# DM2080_Power_Supply.net
KiCad netlist of a schematic drawn in Altium Designer
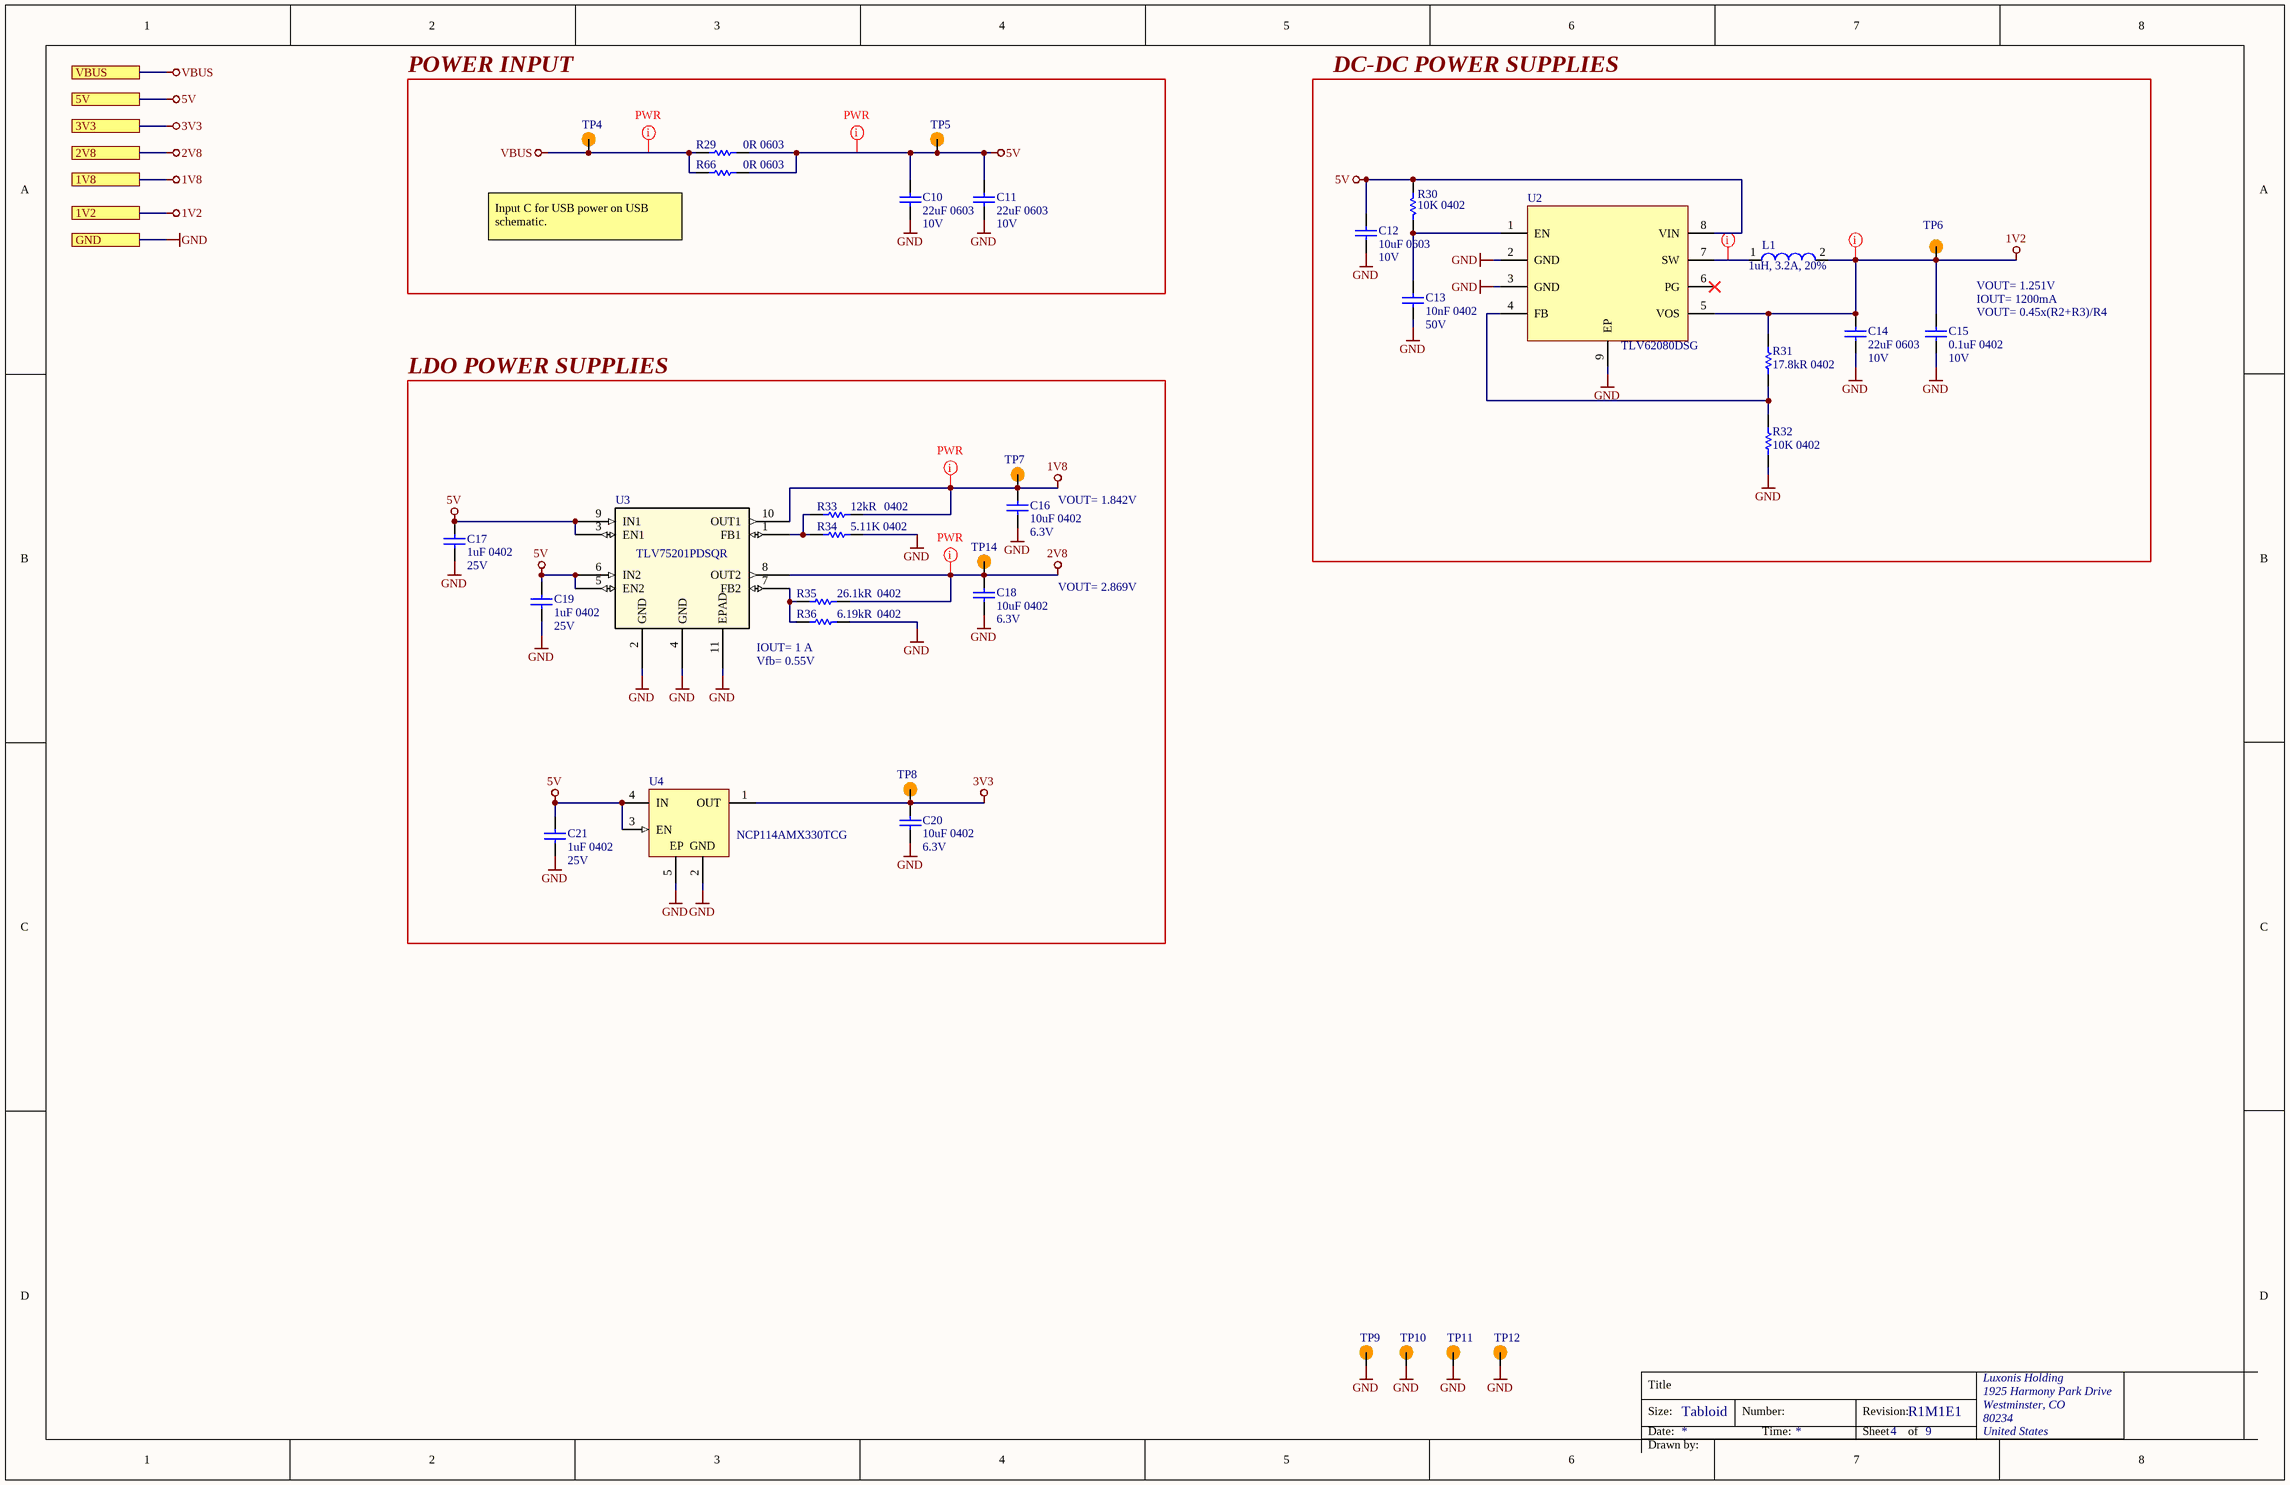
[diagram p0: DM2080_Power_Supply.SchDoc]

(export (version "E")
  (design (tool "Eeschema 10.0.6"))
  (components
    (comp (ref "C10")
      (value "22uF 0603")
      (footprint "CAP_Altium_Vault_Generic:CAPC0603(1608)100_L")
      (description "CAP CER 22UF 10V X5R 0603 20%")
      (fields (field (name "TOLERANCE") "20%") (field (name "VOLTAGE RATING") "10V"))
      (libsource (lib "LuxonisMaster") (part "GRM188R61A226ME15D"))
    )
    (comp (ref "C11")
      (value "22uF 0603")
      (footprint "CAP_Altium_Vault_Generic:CAPC0603(1608)100_L")
      (description "CAP CER 22UF 10V X5R 0603 20%")
      (fields (field (name "TOLERANCE") "20%") (field (name "VOLTAGE RATING") "10V"))
      (libsource (lib "LuxonisMaster") (part "GRM188R61A226ME15D"))
    )
    (comp (ref "C12")
      (value "10uF 0603")
      (footprint "CAP_Altium_Vault_Generic:CAPC0603(1608)100_L")
      (description "CAP CER 10UF 10V X5R 0603 20%")
      (fields (field (name "TOLERANCE") "20%") (field (name "VOLTAGE RATING") "10V"))
      (libsource (lib "LuxonisMaster") (part "GRM188R61A106ME69D"))
    )
    (comp (ref "C13")
      (value "10nF 0402")
      (footprint "CAP_Altium_Vault_Generic:CAPC0402(1005)60_L")
      (description "CAP CER 10000PF 50V X7R 0402")
      (fields
        (field (name "TOLERANCE") "10%")
        (field (name "VOLTAGE") "25V")
        (field (name "VOLTAGE RATING") "50V")
      )
      (libsource (lib "LuxonisMaster") (part "GRM155R71H103KA88D"))
    )
    (comp (ref "C14")
      (value "22uF 0603")
      (footprint "CAP_Altium_Vault_Generic:CAPC0603(1608)100_L")
      (description "CAP CER 22UF 10V X5R 0603 20%")
      (fields (field (name "TOLERANCE") "20%") (field (name "VOLTAGE RATING") "10V"))
      (libsource (lib "LuxonisMaster") (part "GRM188R61A226ME15D"))
    )
    (comp (ref "C15")
      (value "0.1uF 0402")
      (footprint "CAP_Altium_Vault_Generic:CAPC0402(1005)70_L")
      (description "CAP CER 0.1UF 10V X7R 0402 5%")
      (fields (field (name "TOLERANCE") "5%") (field (name "VOLTAGE RATING") "10V"))
      (libsource (lib "LuxonisMaster") (part "GRM155R71A104JA01D"))
    )
    (comp (ref "C16")
      (value "10uF 0402")
      (footprint "CAP_Altium_Vault_Generic:CAPC0402(1005)70_L")
      (description "CAP CER 10UF 6.3V X5R 0402 20%")
      (fields (field (name "TOLERANCE") "20%") (field (name "VOLTAGE RATING") "6.3V"))
      (libsource (lib "LuxonisMaster") (part "GRM155R60J106ME15D"))
    )
    (comp (ref "C17")
      (value "1uF 0402")
      (footprint "CAP_Altium_Vault_Generic:CAPC0402(1005)70_L")
      (description "CAP CER 1UF 25V X5R 0402 10%")
      (fields
        (field (name "TOLERANCE") "10%")
        (field (name "VOLTAGE RATING") "25V")
        (field (name "VOLTAGE") "25V")
      )
      (libsource (lib "LuxonisMaster") (part "GRM155R61E105KA12D"))
    )
    (comp (ref "C18")
      (value "10uF 0402")
      (footprint "CAP_Altium_Vault_Generic:CAPC0402(1005)70_L")
      (description "CAP CER 10UF 6.3V X5R 0402 20%")
      (fields (field (name "TOLERANCE") "20%") (field (name "VOLTAGE RATING") "6.3V"))
      (libsource (lib "LuxonisMaster") (part "GRM155R60J106ME15D"))
    )
    (comp (ref "C19")
      (value "1uF 0402")
      (footprint "CAP_Altium_Vault_Generic:CAPC0402(1005)70_L")
      (description "CAP CER 1UF 25V X5R 0402 10%")
      (fields
        (field (name "TOLERANCE") "10%")
        (field (name "VOLTAGE RATING") "25V")
        (field (name "VOLTAGE") "25V")
      )
      (libsource (lib "LuxonisMaster") (part "GRM155R61E105KA12D"))
    )
    (comp (ref "C20")
      (value "10uF 0402")
      (footprint "CAP_Altium_Vault_Generic:CAPC0402(1005)70_L")
      (description "CAP CER 10UF 6.3V X5R 0402 20%")
      (fields (field (name "TOLERANCE") "20%") (field (name "VOLTAGE RATING") "6.3V"))
      (libsource (lib "LuxonisMaster") (part "GRM155R60J106ME15D"))
    )
    (comp (ref "C21")
      (value "1uF 0402")
      (footprint "CAP_Altium_Vault_Generic:CAPC0402(1005)70_L")
      (description "CAP CER 1UF 25V X5R 0402 10%")
      (fields
        (field (name "TOLERANCE") "10%")
        (field (name "VOLTAGE RATING") "25V")
        (field (name "VOLTAGE") "25V")
      )
      (libsource (lib "LuxonisMaster") (part "GRM155R61E105KA12D"))
    )
    (comp (ref "L1")
      (value "1uH, 3.2A, 20%")
      (footprint "LuxonisMaster:DFE252012P-1R0M=P2")
      (description "FIXED IND 1UH 3.2A 42 MOHM SMD")
      (fields (field (name "TOLERANCE") "20%") (field (name "MANUFACTURER") "Murata"))
      (libsource (lib "LuxonisMaster") (part "DFE252012P-1R0M=P2"))
    )
    (comp (ref "R29")
      (value "0R 0603")
      (footprint "RES_Altium_Vault_Generic:RESC0603(1608)_N")
      (fields (field (name "TOLERANCE") "5%"))
      (libsource (lib "LuxonisMaster") (part "CRCW06030000Z0EA"))
    )
    (comp (ref "R30")
      (value "10K 0402")
      (footprint "RES_Altium_Vault_Generic:RESC0402(1005)_L")
      (fields (field (name "TOLERANCE") "1%"))
      (libsource (lib "LuxonisMaster") (part "RC0402FR-1310KL"))
    )
    (comp (ref "R31")
      (value "ERJ-2RKF1782X")
      (footprint "RESC0402(1005)_L")
      (fields
        (field (name "CASE/PACKAGE") "0402")
        (field (name "TOLERANCE") "1%")
        (field (name "RESISTANCE") "17.8kR")
      )
      (libsource (lib "Luxonis LLC") (part "CR0402-FX-2492GLF"))
    )
    (comp (ref "R32")
      (value "10K 0402")
      (footprint "RES_Altium_Vault_Generic:RESC0402(1005)_L")
      (description "RES SMD 10K OHM 1% 1/16W 0402")
      (fields (field (name "TOLERANCE") "1%"))
      (libsource (lib "LuxonisMaster") (part "RC0402FR-1310KL"))
    )
    (comp (ref "R33")
      (value "RC0402FR-0712KL")
      (footprint "RESC0402(1005)_L")
      (fields
        (field (name "TOLERANCE") "1%")
        (field (name "RESISTANCE") "12kR")
        (field (name "CASE/PACKAGE") "0402")
      )
      (libsource (lib "Luxonis LLC") (part "CR0402-FX-2492GLF"))
    )
    (comp (ref "R34")
      (value "5.11K 0402")
      (footprint "RES_Altium_Vault_Generic:RESC0402(1005)_L")
      (fields (field (name "TOLERANCE") "1%"))
      (libsource (lib "LuxonisMaster") (part "RC0402FR-075K11L"))
    )
    (comp (ref "R35")
      (value "RC0402FR-0726K1L")
      (footprint "RESC0402(1005)_L")
      (description "RES SMD 26.1K OHM 1% 1/16W 0402")
      (fields
        (field (name "CASE/PACKAGE") "0402")
        (field (name "TOLERANCE") "1%")
        (field (name "RESISTANCE") "26.1kR")
      )
      (libsource (lib "Luxonis LLC") (part "RC0402FR-0726K1L"))
    )
    (comp (ref "R36")
      (value "RC0402FR-076K19L")
      (footprint "RESC0402(1005)_L")
      (description "RES SMD 6.19K 1% 1/16W 0402")
      (fields
        (field (name "RESISTANCE") "6.19kR")
        (field (name "CASE/PACKAGE") "0402")
        (field (name "TOLERANCE") "1%")
      )
      (libsource (lib "Luxonis LLC") (part "CR0402-FX-2492GLF"))
    )
    (comp (ref "R66")
      (value "0R 0603")
      (footprint "RES_Altium_Vault_Generic:RESC0603(1608)_N")
      (fields (field (name "TOLERANCE") "5%"))
      (libsource (lib "LuxonisMaster") (part "CRCW06030000Z0EA"))
    )
    (comp (ref "TP4")
      (value "TP100_200_NS")
      (footprint "LuxonisMaster:TP100_200_NS")
      (libsource (lib "LuxonisMaster") (part "TEST_POINT"))
    )
    (comp (ref "TP5")
      (value "TP100_200_NS")
      (footprint "LuxonisMaster:TP100_200_NS")
      (libsource (lib "LuxonisMaster") (part "TEST_POINT"))
    )
    (comp (ref "TP6")
      (value "TP075_150_NS")
      (footprint "LuxonisMaster:TP075_150_NS")
      (libsource (lib "LuxonisMaster") (part "TEST_POINT"))
    )
    (comp (ref "TP7")
      (value "TP075_150_NS")
      (footprint "LuxonisMaster:TP075_150_NS")
      (libsource (lib "LuxonisMaster") (part "TEST_POINT"))
    )
    (comp (ref "TP8")
      (value "TP075_150_NS")
      (footprint "LuxonisMaster:TP075_150_NS")
      (libsource (lib "LuxonisMaster") (part "TEST_POINT"))
    )
    (comp (ref "TP9")
      (value "TP100_200_NS")
      (footprint "LuxonisMaster:TP100_200_NS")
      (libsource (lib "LuxonisMaster") (part "TEST_POINT"))
    )
    (comp (ref "TP10")
      (value "TP100_200_NS")
      (footprint "LuxonisMaster:TP100_200_NS")
      (libsource (lib "LuxonisMaster") (part "TEST_POINT"))
    )
    (comp (ref "TP11")
      (value "TP100_200_NS")
      (footprint "LuxonisMaster:TP100_200_NS")
      (libsource (lib "LuxonisMaster") (part "TEST_POINT"))
    )
    (comp (ref "TP12")
      (value "TP100_200_NS")
      (footprint "LuxonisMaster:TP100_200_NS")
      (libsource (lib "LuxonisMaster") (part "TEST_POINT"))
    )
    (comp (ref "TP14")
      (value "TP075_150_NS")
      (footprint "LuxonisMaster:TP075_150_NS")
      (libsource (lib "LuxonisMaster") (part "TEST_POINT"))
    )
    (comp (ref "U2")
      (value "TLV62080DSG")
      (footprint "LuxonisMaster:TLV62080DSG")
      (description "IC REG BUCK ADJ 1.2A SYNC 8WSON")
      (libsource (lib "LuxonisMaster") (part "TLV62080DSG"))
    )
    (comp (ref "U3")
      (value "TLV75201PDSQR")
      (footprint "SON_1PDSQR_TEX")
      (description "TLV752 Dual, 1-A, High-Accuracy, Adjustable-LDO in a Small-Size Package")
      (fields (field (name "COPYRIGHT") "Copyright (C) 2021 Ultra Librarian. All rights reserved."))
      (libsource (lib "altium-import") (part "root_0_TLV75201PDSQR_"))
    )
    (comp (ref "U4")
      (value "NCP114AMX330TCG")
      (footprint "DQN0004A_V")
      (description "LDO Regulator, 300 mA, High PSRR 3.3V, Active Discharge")
      (fields (field (name "MANUFACTURER PART NUMBER 1") "NCP114AMX330TCG"))
      (libsource (lib "Luxonis LLC") (part "TI-TLV707XXX-DQN4-480X480TP"))
    )
  )
  (nets
    (net (code "1") (name "1V2") (class "Default")
      (node (ref "C14") (pin "2") (pinfunction "2_2") (pintype "passive"))
      (node (ref "C15") (pin "2") (pinfunction "2_2") (pintype "passive"))
      (node (ref "L1") (pin "2") (pinfunction "2_2") (pintype "passive"))
      (node (ref "R31") (pin "2") (pinfunction "2_2") (pintype "passive"))
      (node (ref "TP6") (pin "1") (pintype "passive"))
      (node (ref "U2") (pin "5") (pinfunction "VOS_5") (pintype "passive"))
    )
    (net (code "2") (name "1V8") (class "Default")
      (node (ref "C16") (pin "2") (pinfunction "2_2") (pintype "passive"))
      (node (ref "R33") (pin "2") (pinfunction "2_2") (pintype "passive"))
      (node (ref "TP7") (pin "1") (pintype "passive"))
      (node (ref "U3") (pin "10") (pinfunction "OUT1_10") (pintype "output"))
    )
    (net (code "3") (name "2V8") (class "Default")
      (node (ref "C18") (pin "2") (pinfunction "2_2") (pintype "passive"))
      (node (ref "R35") (pin "2") (pinfunction "2_2") (pintype "passive"))
      (node (ref "TP14") (pin "1") (pintype "passive"))
      (node (ref "U3") (pin "8") (pinfunction "OUT2_8") (pintype "output"))
    )
    (net (code "4") (name "3V3") (class "Default")
      (node (ref "C20") (pin "2") (pinfunction "2_2") (pintype "passive"))
      (node (ref "TP8") (pin "1") (pintype "passive"))
      (node (ref "U4") (pin "1") (pinfunction "OUT_1") (pintype "power_in"))
    )
    (net (code "5") (name "5V") (class "Default")
      (node (ref "C10") (pin "2") (pinfunction "2_2") (pintype "passive"))
      (node (ref "C11") (pin "2") (pinfunction "2_2") (pintype "passive"))
      (node (ref "C12") (pin "2") (pinfunction "2_2") (pintype "passive"))
      (node (ref "C17") (pin "1") (pinfunction "1_1") (pintype "passive"))
      (node (ref "C19") (pin "1") (pinfunction "1_1") (pintype "passive"))
      (node (ref "C21") (pin "1") (pinfunction "1_1") (pintype "passive"))
      (node (ref "R29") (pin "2") (pinfunction "2_2") (pintype "passive"))
      (node (ref "R30") (pin "2") (pinfunction "2_2") (pintype "passive"))
      (node (ref "R66") (pin "2") (pinfunction "2_2") (pintype "passive"))
      (node (ref "TP5") (pin "1") (pintype "passive"))
      (node (ref "U2") (pin "8") (pinfunction "VIN_8") (pintype "passive"))
      (node (ref "U3") (pin "3") (pinfunction "EN1_3") (pintype "bidirectional"))
      (node (ref "U3") (pin "5") (pinfunction "EN2_5") (pintype "bidirectional"))
      (node (ref "U3") (pin "6") (pinfunction "IN2_6") (pintype "input"))
      (node (ref "U3") (pin "9") (pinfunction "IN1_9") (pintype "input"))
      (node (ref "U4") (pin "3") (pinfunction "EN_3") (pintype "input"))
      (node (ref "U4") (pin "4") (pinfunction "IN_4") (pintype "power_in"))
    )
    (net (code "6") (name "GND") (class "Default")
      (node (ref "C10") (pin "1") (pinfunction "1_1") (pintype "passive"))
      (node (ref "C11") (pin "1") (pinfunction "1_1") (pintype "passive"))
      (node (ref "C12") (pin "1") (pinfunction "1_1") (pintype "passive"))
      (node (ref "C13") (pin "1") (pinfunction "1_1") (pintype "passive"))
      (node (ref "C14") (pin "1") (pinfunction "1_1") (pintype "passive"))
      (node (ref "C15") (pin "1") (pinfunction "1_1") (pintype "passive"))
      (node (ref "C16") (pin "1") (pinfunction "1_1") (pintype "passive"))
      (node (ref "C17") (pin "2") (pinfunction "2_2") (pintype "passive"))
      (node (ref "C18") (pin "1") (pinfunction "1_1") (pintype "passive"))
      (node (ref "C19") (pin "2") (pinfunction "2_2") (pintype "passive"))
      (node (ref "C20") (pin "1") (pinfunction "1_1") (pintype "passive"))
      (node (ref "C21") (pin "2") (pinfunction "2_2") (pintype "passive"))
      (node (ref "R32") (pin "1") (pinfunction "1_1") (pintype "passive"))
      (node (ref "R34") (pin "2") (pinfunction "2_2") (pintype "passive"))
      (node (ref "R36") (pin "2") (pinfunction "2_2") (pintype "passive"))
      (node (ref "TP10") (pin "1") (pintype "passive"))
      (node (ref "TP11") (pin "1") (pintype "passive"))
      (node (ref "TP12") (pin "1") (pintype "passive"))
      (node (ref "TP9") (pin "1") (pintype "passive"))
      (node (ref "U2") (pin "2") (pinfunction "GND_2") (pintype "passive"))
      (node (ref "U2") (pin "3") (pinfunction "GND_3") (pintype "passive"))
      (node (ref "U2") (pin "9") (pinfunction "EP_9") (pintype "passive"))
      (node (ref "U3") (pin "11") (pinfunction "EPAD_11") (pintype "passive"))
      (node (ref "U3") (pin "2") (pinfunction "GND_2") (pintype "passive"))
      (node (ref "U3") (pin "4") (pinfunction "GND_4") (pintype "passive"))
      (node (ref "U4") (pin "2") (pinfunction "GND_2") (pintype "power_in"))
      (node (ref "U4") (pin "5") (pinfunction "EP_5") (pintype "passive"))
    )
    (net (code "7") (name "Net-(U2-EN)") (class "Default")
      (node (ref "C13") (pin "2") (pinfunction "2_2") (pintype "passive"))
      (node (ref "R30") (pin "1") (pinfunction "1_1") (pintype "passive"))
      (node (ref "U2") (pin "1") (pinfunction "EN_1") (pintype "passive"))
    )
    (net (code "8") (name "Net-(U2-FB)") (class "Default")
      (node (ref "R31") (pin "1") (pinfunction "1_1") (pintype "passive"))
      (node (ref "R32") (pin "2") (pinfunction "2_2") (pintype "passive"))
      (node (ref "U2") (pin "4") (pinfunction "FB_4") (pintype "passive"))
    )
    (net (code "9") (name "Net-(U2-SW)") (class "Default")
      (node (ref "L1") (pin "1") (pinfunction "1_1") (pintype "passive"))
      (node (ref "U2") (pin "7") (pinfunction "SW_7") (pintype "passive"))
    )
    (net (code "10") (name "Net-(U3-FB1)") (class "Default")
      (node (ref "R33") (pin "1") (pinfunction "1_1") (pintype "passive"))
      (node (ref "R34") (pin "1") (pinfunction "1_1") (pintype "passive"))
      (node (ref "U3") (pin "1") (pinfunction "FB1_1") (pintype "bidirectional"))
    )
    (net (code "11") (name "Net-(U3-FB2)") (class "Default")
      (node (ref "R35") (pin "1") (pinfunction "1_1") (pintype "passive"))
      (node (ref "R36") (pin "1") (pinfunction "1_1") (pintype "passive"))
      (node (ref "U3") (pin "7") (pinfunction "FB2_7") (pintype "bidirectional"))
    )
    (net (code "12") (name "VBUS") (class "Default")
      (node (ref "R29") (pin "1") (pinfunction "1_1") (pintype "passive"))
      (node (ref "R66") (pin "1") (pinfunction "1_1") (pintype "passive"))
      (node (ref "TP4") (pin "1") (pintype "passive"))
    )
    (net (code "13") (name "unconnected-(U2-PG-Pad6)") (class "Default")
      (node (ref "U2") (pin "6") (pinfunction "PG_6") (pintype "passive+no_connect"))
    )
  )
)
